# Detect_IR_v2_SCH.net
KiCad netlist of a schematic drawn in Altium Designer
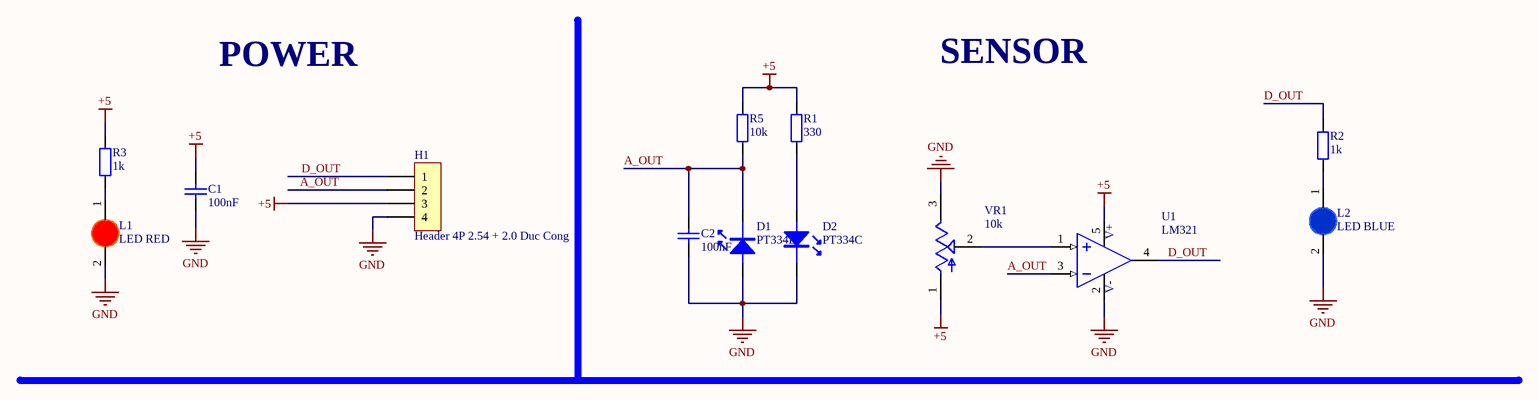
[diagram p0: Detect_IR_v2_SCH.SchDoc]

(export (version "E")
  (design (tool "Eeschema 10.0.6"))
  (components
    (comp (ref "C1")
      (value "100nF")
      (footprint "tu 0603")
      (description "Dán")
      (libsource (lib "namnt_Lib") (part "Tu 0603 104 50V 10%"))
    )
    (comp (ref "C2")
      (value "100nF")
      (footprint "tu 0603")
      (description "Dán")
      (libsource (lib "namnt_Lib") (part "Tu 0603 104 50V 10%"))
    )
    (comp (ref "D1")
      (value "PT334B")
      (footprint "xlib:LED_CIRCLE_DIP_2P_5MM")
      (description "Led")
      (libsource (lib "XLib") (part "LED_DIP_2P"))
    )
    (comp (ref "D2")
      (value "PT334C")
      (footprint "xlib:LED_CIRCLE_DIP_2P_5MM")
      (description "Led")
      (libsource (lib "XLib") (part "LED_DIP_2P"))
    )
    (comp (ref "H1")
      (value "Header 4P 2.54 + 2.0 Duc Cong")
      (footprint "Header 4P DC 2.54 + 2.0")
      (description "Cắm")
      (libsource (lib "namnt_Lib") (part "Header 4P 2.54 + 2.0 Duc Cong"))
    )
    (comp (ref "L1")
      (value "LED RED")
      (footprint "LED-0805-Red")
      (description "Dán")
      (libsource (lib "namnt_Lib") (part "LED 0805 Do"))
    )
    (comp (ref "L2")
      (value "LED BLUE")
      (footprint "LED-0805-Blue")
      (description "Dán")
      (libsource (lib "namnt_Lib") (part "LED 0805 Xanh Duong"))
    )
    (comp (ref "R1")
      (value "330")
      (footprint "tro smd 0603")
      (description "Dán")
      (libsource (lib "namnt_Lib") (part "Tro 0603 1% 10k"))
    )
    (comp (ref "R2")
      (value "1k")
      (footprint "tro smd 0603")
      (description "Dán")
      (libsource (lib "namnt_Lib") (part "Tro 0603 1% 1k"))
    )
    (comp (ref "R3")
      (value "1k")
      (footprint "tro smd 0603")
      (description "Dán")
      (libsource (lib "namnt_Lib") (part "Tro 0603 1% 1k"))
    )
    (comp (ref "R5")
      (value "10k")
      (footprint "tro smd 0603")
      (description "Dán")
      (libsource (lib "namnt_Lib") (part "Tro 0603 1% 10k"))
    )
    (comp (ref "U1")
      (value "LM321")
      (footprint "xlib:sot23-5")
      (description "Opamp")
      (libsource (lib "XLib") (part "LM321"))
    )
    (comp (ref "VR1")
      (value "10k")
      (footprint "TRIM_3362P-1-102")
      (description "TRIMMER - 1/4in SQ ST CERMET ¦ Bourns 3362P-1-102")
      (fields (field (name "MF") "Bourns") (field (name "MP") "3362P-1-102"))
      (libsource (lib "namnt_Lib") (part "Bien tro vuong"))
    )
  )
  (nets
    (net (code "1") (name "+5") (class "Default")
      (node (ref "C1") (pin "1") (pinfunction "1_1") (pintype "passive"))
      (node (ref "H1") (pin "3") (pinfunction "3_3") (pintype "passive"))
      (node (ref "R1") (pin "2") (pinfunction "2_2") (pintype "passive"))
      (node (ref "R3") (pin "2") (pinfunction "2_2") (pintype "passive"))
      (node (ref "R5") (pin "2") (pinfunction "2_2") (pintype "passive"))
      (node (ref "U1") (pin "5") (pinfunction "V+_5") (pintype "power_in"))
      (node (ref "VR1") (pin "1") (pinfunction "CCW_1") (pintype "passive"))
    )
    (net (code "2") (name "/A_OUT") (class "Default")
      (node (ref "C2") (pin "1") (pinfunction "1_1") (pintype "passive"))
      (node (ref "D1") (pin "2") (pinfunction "2_2") (pintype "passive"))
      (node (ref "H1") (pin "2") (pinfunction "2_2") (pintype "passive"))
      (node (ref "R5") (pin "1") (pinfunction "1_1") (pintype "passive"))
      (node (ref "U1") (pin "3") (pinfunction "IN-_3") (pintype "input"))
    )
    (net (code "3") (name "/D_OUT") (class "Default")
      (node (ref "H1") (pin "1") (pinfunction "1_1") (pintype "passive"))
      (node (ref "R2") (pin "2") (pinfunction "2_2") (pintype "passive"))
      (node (ref "U1") (pin "4") (pinfunction "-V_4") (pintype "passive"))
    )
    (net (code "4") (name "GND") (class "Default")
      (node (ref "C1") (pin "2") (pinfunction "2_2") (pintype "passive"))
      (node (ref "C2") (pin "2") (pinfunction "2_2") (pintype "passive"))
      (node (ref "D1") (pin "1") (pinfunction "1_1") (pintype "passive"))
      (node (ref "D2") (pin "2") (pinfunction "2_2") (pintype "passive"))
      (node (ref "H1") (pin "4") (pinfunction "4_4") (pintype "passive"))
      (node (ref "L1") (pin "2") (pinfunction "K_2") (pintype "passive"))
      (node (ref "L2") (pin "2") (pinfunction "K_2") (pintype "passive"))
      (node (ref "U1") (pin "2") (pinfunction "V-_2") (pintype "power_in"))
      (node (ref "VR1") (pin "3") (pinfunction "CW_3") (pintype "passive"))
    )
    (net (code "5") (name "Net-(D2-Pad1)") (class "Default")
      (node (ref "D2") (pin "1") (pinfunction "1_1") (pintype "passive"))
      (node (ref "R1") (pin "1") (pinfunction "1_1") (pintype "passive"))
    )
    (net (code "6") (name "Net-(L1-A)") (class "Default")
      (node (ref "L1") (pin "1") (pinfunction "A_1") (pintype "passive"))
      (node (ref "R3") (pin "1") (pinfunction "1_1") (pintype "passive"))
    )
    (net (code "7") (name "Net-(L2-A)") (class "Default")
      (node (ref "L2") (pin "1") (pinfunction "A_1") (pintype "passive"))
      (node (ref "R2") (pin "1") (pinfunction "1_1") (pintype "passive"))
    )
    (net (code "8") (name "Net-(U1-IN+)") (class "Default")
      (node (ref "U1") (pin "1") (pinfunction "IN+_1") (pintype "input"))
      (node (ref "VR1") (pin "2") (pinfunction "WIPER_2") (pintype "passive"))
    )
  )
)
